# control_unit_0.net
KiCad netlist of a schematic drawn in EAGLE
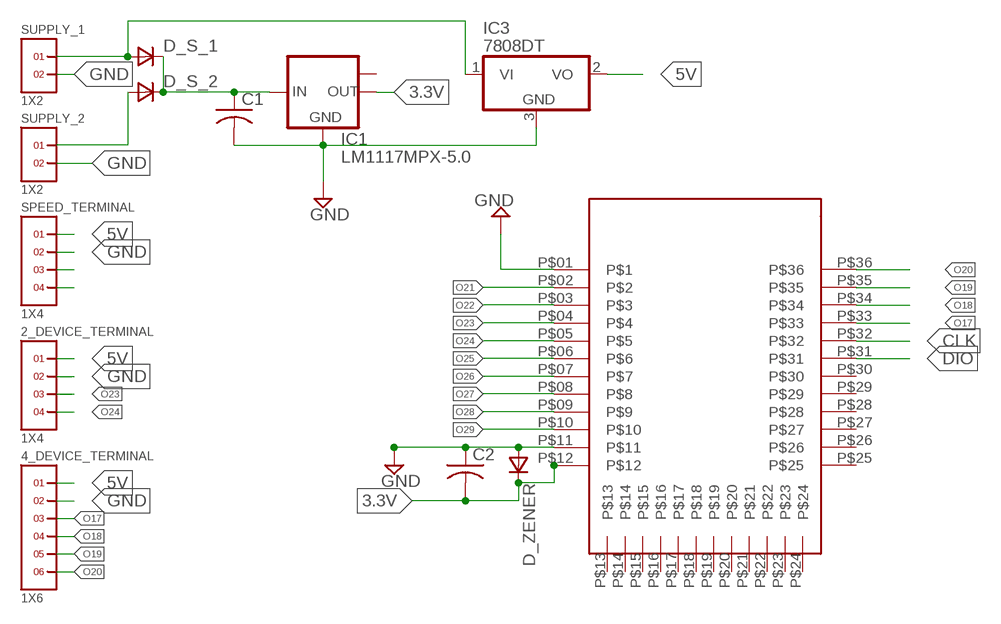
[diagram p0: schematic, sheet 1]

(export (version "E")
  (design (tool "Eeschema 10.0.6"))
  (components
    (comp (ref "2_DEVICE_TERMINAL")
      (value "1X4")
      (footprint "eagle-import:1X4")
      (libsource (lib "eagle-import") (part "1X4"))
    )
    (comp (ref "4_DEVICE_TERMINAL")
      (value "1X6")
      (footprint "eagle-import:1X6")
      (libsource (lib "eagle-import") (part "1X6"))
    )
    (comp (ref "C1")
      (value "C-USC1206")
      (footprint "eagle-import:C1206")
      (libsource (lib "eagle-import") (part "C-USC1206"))
    )
    (comp (ref "C2")
      (value "C-USC1206")
      (footprint "eagle-import:C1206")
      (libsource (lib "eagle-import") (part "C-USC1206"))
    )
    (comp (ref "D_S_1")
      (value "DSOD323")
      (footprint "eagle-import:SOD323")
      (fields (field (name "MPN") "CDSOD323-T05C"))
      (libsource (lib "eagle-import") (part "DSOD323"))
    )
    (comp (ref "D_S_2")
      (value "DSOD323")
      (footprint "eagle-import:SOD323")
      (fields (field (name "MPN") "CDSOD323-T05C"))
      (libsource (lib "eagle-import") (part "DSOD323"))
    )
    (comp (ref "D_ZENER")
      (value "DSOD323")
      (footprint "eagle-import:SOD323")
      (fields (field (name "MPN") "CDSOD323-T05C"))
      (libsource (lib "eagle-import") (part "DSOD323"))
    )
    (comp (ref "IC1")
      (value "LM1117MPX-5.0")
      (footprint "eagle-import:SOT223")
      (libsource (lib "eagle-import") (part "LM1117MPX-5.0"))
    )
    (comp (ref "IC3")
      (value "7808DT")
      (footprint "eagle-import:TO252")
      (libsource (lib "eagle-import") (part "78DT08"))
    )
    (comp (ref "SPEED_TERMINAL")
      (value "1X4")
      (footprint "eagle-import:1X4")
      (libsource (lib "eagle-import") (part "1X4"))
    )
    (comp (ref "SUPPLY_1")
      (value "1X2")
      (footprint "eagle-import:1X2")
      (libsource (lib "eagle-import") (part "1X2"))
    )
    (comp (ref "SUPPLY_2")
      (value "1X2")
      (footprint "eagle-import:1X2")
      (libsource (lib "eagle-import") (part "1X2"))
    )
    (comp (ref "U$1")
      (value "HZX_MODULE")
      (footprint "eagle-import:SMD_PAD_VERSION")
      (fields (field (name "AUTHOR") "Agam"))
      (libsource (lib "eagle-import") (part "HZX_MODULE"))
    )
  )
  (nets
    (net (code "1") (name "3.3V") (class "Default")
      (node (ref "C2") (pin "2") (pinfunction "2_2") (pintype "passive"))
      (node (ref "D_ZENER") (pin "1") (pinfunction "C_1") (pintype "passive"))
      (node (ref "IC1") (pin "2") (pinfunction "OUT_2") (pintype "passive"))
      (node (ref "U$1") (pin "P$12") (pinfunction "P$12_P$12") (pintype "bidirectional"))
    )
    (net (code "2") (name "5V") (class "Default")
      (node (ref "2_DEVICE_TERMINAL") (pin "1") (pinfunction "1_1") (pintype "bidirectional"))
      (node (ref "4_DEVICE_TERMINAL") (pin "1") (pinfunction "1_1") (pintype "bidirectional"))
      (node (ref "IC3") (pin "2") (pinfunction "VO_2") (pintype "passive"))
      (node (ref "SPEED_TERMINAL") (pin "1") (pinfunction "1_1") (pintype "bidirectional"))
    )
    (net (code "3") (name "CLK") (class "Default")
      (node (ref "U$1") (pin "P$32") (pinfunction "P$32_P$32") (pintype "bidirectional"))
    )
    (net (code "4") (name "DIO") (class "Default")
      (node (ref "U$1") (pin "P$31") (pinfunction "P$31_P$31") (pintype "bidirectional"))
    )
    (net (code "5") (name "GND") (class "Default")
      (node (ref "2_DEVICE_TERMINAL") (pin "2") (pinfunction "2_2") (pintype "bidirectional"))
      (node (ref "4_DEVICE_TERMINAL") (pin "2") (pinfunction "2_2") (pintype "bidirectional"))
      (node (ref "C1") (pin "2") (pinfunction "2_2") (pintype "passive"))
      (node (ref "C2") (pin "1") (pinfunction "1_1") (pintype "passive"))
      (node (ref "D_ZENER") (pin "2") (pinfunction "A_2") (pintype "passive"))
      (node (ref "IC1") (pin "1") (pinfunction "GND_1") (pintype "input"))
      (node (ref "IC3") (pin "3") (pinfunction "GND_3") (pintype "passive"))
      (node (ref "SPEED_TERMINAL") (pin "2") (pinfunction "2_2") (pintype "bidirectional"))
      (node (ref "SUPPLY_1") (pin "2") (pinfunction "2_2") (pintype "bidirectional"))
      (node (ref "SUPPLY_2") (pin "2") (pinfunction "2_2") (pintype "bidirectional"))
      (node (ref "U$1") (pin "P$01") (pinfunction "P$1_P$01") (pintype "bidirectional"))
      (node (ref "U$1") (pin "P$11") (pinfunction "P$11_P$11") (pintype "bidirectional"))
    )
    (net (code "6") (name "Net-(D_S_1-A)") (class "Default")
      (node (ref "D_S_1") (pin "2") (pinfunction "A_2") (pintype "passive"))
      (node (ref "IC3") (pin "1") (pinfunction "VI_1") (pintype "input"))
      (node (ref "SUPPLY_1") (pin "1") (pinfunction "1_1") (pintype "bidirectional"))
    )
    (net (code "7") (name "Net-(D_S_1-C)") (class "Default")
      (node (ref "C1") (pin "1") (pinfunction "1_1") (pintype "passive"))
      (node (ref "D_S_1") (pin "1") (pinfunction "C_1") (pintype "passive"))
      (node (ref "D_S_2") (pin "1") (pinfunction "C_1") (pintype "passive"))
      (node (ref "IC1") (pin "3") (pinfunction "IN_3") (pintype "input"))
    )
    (net (code "8") (name "Net-(D_S_2-A)") (class "Default")
      (node (ref "D_S_2") (pin "2") (pinfunction "A_2") (pintype "passive"))
      (node (ref "SUPPLY_2") (pin "1") (pinfunction "1_1") (pintype "bidirectional"))
    )
    (net (code "9") (name "O17") (class "Default")
      (node (ref "4_DEVICE_TERMINAL") (pin "3") (pinfunction "3_3") (pintype "bidirectional"))
      (node (ref "U$1") (pin "P$33") (pinfunction "P$33_P$33") (pintype "bidirectional"))
    )
    (net (code "10") (name "O18") (class "Default")
      (node (ref "4_DEVICE_TERMINAL") (pin "4") (pinfunction "4_4") (pintype "bidirectional"))
      (node (ref "U$1") (pin "P$34") (pinfunction "P$34_P$34") (pintype "bidirectional"))
    )
    (net (code "11") (name "O19") (class "Default")
      (node (ref "4_DEVICE_TERMINAL") (pin "5") (pinfunction "5_5") (pintype "bidirectional"))
      (node (ref "U$1") (pin "P$35") (pinfunction "P$35_P$35") (pintype "bidirectional"))
    )
    (net (code "12") (name "O20") (class "Default")
      (node (ref "4_DEVICE_TERMINAL") (pin "6") (pinfunction "6_6") (pintype "bidirectional"))
      (node (ref "U$1") (pin "P$36") (pinfunction "P$36_P$36") (pintype "bidirectional"))
    )
    (net (code "13") (name "O21") (class "Default")
      (node (ref "U$1") (pin "P$02") (pinfunction "P$2_P$02") (pintype "bidirectional"))
    )
    (net (code "14") (name "O22") (class "Default")
      (node (ref "U$1") (pin "P$03") (pinfunction "P$3_P$03") (pintype "bidirectional"))
    )
    (net (code "15") (name "O23") (class "Default")
      (node (ref "2_DEVICE_TERMINAL") (pin "3") (pinfunction "3_3") (pintype "bidirectional"))
      (node (ref "U$1") (pin "P$04") (pinfunction "P$4_P$04") (pintype "bidirectional"))
    )
    (net (code "16") (name "O24") (class "Default")
      (node (ref "2_DEVICE_TERMINAL") (pin "4") (pinfunction "4_4") (pintype "bidirectional"))
      (node (ref "U$1") (pin "P$05") (pinfunction "P$5_P$05") (pintype "bidirectional"))
    )
    (net (code "17") (name "O25") (class "Default")
      (node (ref "U$1") (pin "P$06") (pinfunction "P$6_P$06") (pintype "bidirectional"))
    )
    (net (code "18") (name "O26") (class "Default")
      (node (ref "U$1") (pin "P$07") (pinfunction "P$7_P$07") (pintype "bidirectional"))
    )
    (net (code "19") (name "O27") (class "Default")
      (node (ref "U$1") (pin "P$08") (pinfunction "P$8_P$08") (pintype "bidirectional"))
    )
    (net (code "20") (name "O28") (class "Default")
      (node (ref "U$1") (pin "P$09") (pinfunction "P$9_P$09") (pintype "bidirectional"))
    )
    (net (code "21") (name "O29") (class "Default")
      (node (ref "U$1") (pin "P$10") (pinfunction "P$10_P$10") (pintype "bidirectional"))
    )
    (net (code "22") (name "unconnected-(IC1-OUT1-PadTAB)") (class "Default")
      (node (ref "IC1") (pin "TAB") (pinfunction "OUT1_TAB") (pintype "passive"))
    )
    (net (code "23") (name "unconnected-(SPEED_TERMINAL-Pad3)") (class "Default")
      (node (ref "SPEED_TERMINAL") (pin "3") (pinfunction "3_3") (pintype "bidirectional"))
    )
    (net (code "24") (name "unconnected-(SPEED_TERMINAL-Pad4)") (class "Default")
      (node (ref "SPEED_TERMINAL") (pin "4") (pinfunction "4_4") (pintype "bidirectional"))
    )
    (net (code "25") (name "unconnected-(U$1-PadP$13)") (class "Default")
      (node (ref "U$1") (pin "P$13") (pinfunction "P$13_P$13") (pintype "bidirectional"))
    )
    (net (code "26") (name "unconnected-(U$1-PadP$14)") (class "Default")
      (node (ref "U$1") (pin "P$14") (pinfunction "P$14_P$14") (pintype "bidirectional"))
    )
    (net (code "27") (name "unconnected-(U$1-PadP$15)") (class "Default")
      (node (ref "U$1") (pin "P$15") (pinfunction "P$15_P$15") (pintype "bidirectional"))
    )
    (net (code "28") (name "unconnected-(U$1-PadP$16)") (class "Default")
      (node (ref "U$1") (pin "P$16") (pinfunction "P$16_P$16") (pintype "bidirectional"))
    )
    (net (code "29") (name "unconnected-(U$1-PadP$17)") (class "Default")
      (node (ref "U$1") (pin "P$17") (pinfunction "P$17_P$17") (pintype "bidirectional"))
    )
    (net (code "30") (name "unconnected-(U$1-PadP$18)") (class "Default")
      (node (ref "U$1") (pin "P$18") (pinfunction "P$18_P$18") (pintype "bidirectional"))
    )
    (net (code "31") (name "unconnected-(U$1-PadP$19)") (class "Default")
      (node (ref "U$1") (pin "P$19") (pinfunction "P$19_P$19") (pintype "bidirectional"))
    )
    (net (code "32") (name "unconnected-(U$1-PadP$20)") (class "Default")
      (node (ref "U$1") (pin "P$20") (pinfunction "P$20_P$20") (pintype "bidirectional"))
    )
    (net (code "33") (name "unconnected-(U$1-PadP$21)") (class "Default")
      (node (ref "U$1") (pin "P$21") (pinfunction "P$21_P$21") (pintype "bidirectional"))
    )
    (net (code "34") (name "unconnected-(U$1-PadP$22)") (class "Default")
      (node (ref "U$1") (pin "P$22") (pinfunction "P$22_P$22") (pintype "bidirectional"))
    )
    (net (code "35") (name "unconnected-(U$1-PadP$23)") (class "Default")
      (node (ref "U$1") (pin "P$23") (pinfunction "P$23_P$23") (pintype "bidirectional"))
    )
    (net (code "36") (name "unconnected-(U$1-PadP$24)") (class "Default")
      (node (ref "U$1") (pin "P$24") (pinfunction "P$24_P$24") (pintype "bidirectional"))
    )
    (net (code "37") (name "unconnected-(U$1-PadP$25)") (class "Default")
      (node (ref "U$1") (pin "P$25") (pinfunction "P$25_P$25") (pintype "bidirectional"))
    )
    (net (code "38") (name "unconnected-(U$1-PadP$26)") (class "Default")
      (node (ref "U$1") (pin "P$26") (pinfunction "P$26_P$26") (pintype "bidirectional"))
    )
    (net (code "39") (name "unconnected-(U$1-PadP$27)") (class "Default")
      (node (ref "U$1") (pin "P$27") (pinfunction "P$27_P$27") (pintype "bidirectional"))
    )
    (net (code "40") (name "unconnected-(U$1-PadP$28)") (class "Default")
      (node (ref "U$1") (pin "P$28") (pinfunction "P$28_P$28") (pintype "bidirectional"))
    )
    (net (code "41") (name "unconnected-(U$1-PadP$29)") (class "Default")
      (node (ref "U$1") (pin "P$29") (pinfunction "P$29_P$29") (pintype "bidirectional"))
    )
    (net (code "42") (name "unconnected-(U$1-PadP$30)") (class "Default")
      (node (ref "U$1") (pin "P$30") (pinfunction "P$30_P$30") (pintype "bidirectional"))
    )
  )
)
